# Sheet1.net
KiCad netlist of a schematic drawn in Altium Designer
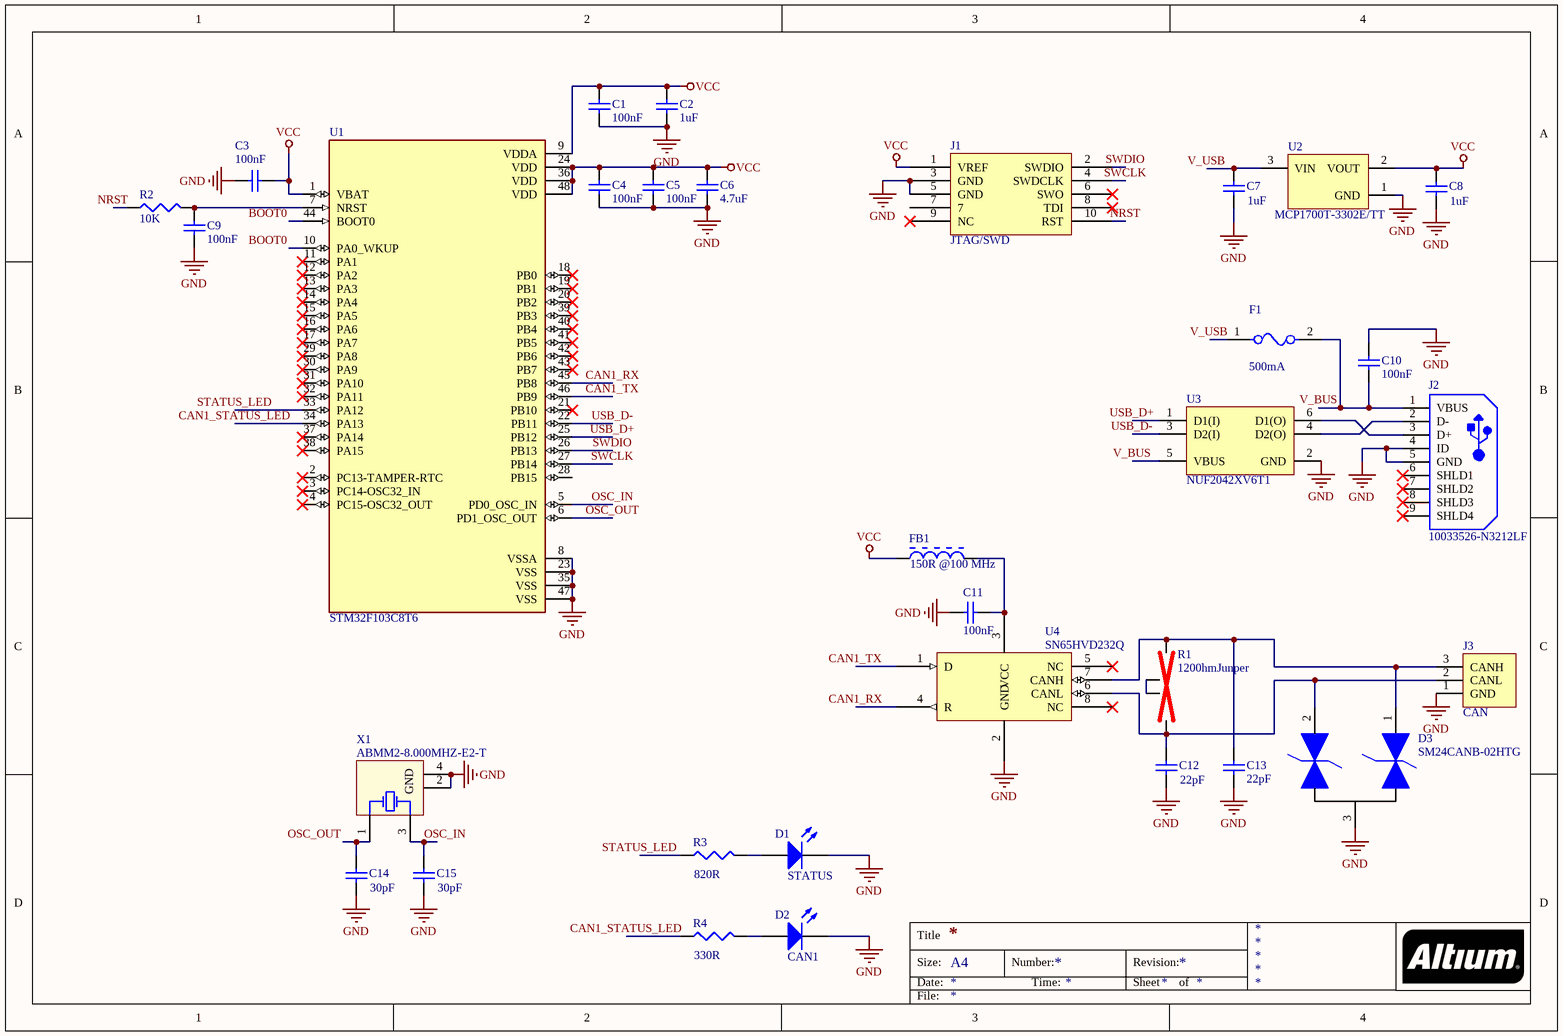
[diagram p0: Sheet1.SchDoc]

(export (version "E")
  (design (tool "Eeschema 10.0.6"))
  (components
    (comp (ref "C1")
      (value "100nF")
      (footprint "CAP0805")
      (description "Capacitor (Semiconductor SIM Model)")
      (fields (field (name "Comment") "Cap Semi") (field (name "PUBLISHER") "Altium Limited"))
      (libsource (lib "Miscellaneous Devices") (part "Cap Semi"))
    )
    (comp (ref "C2")
      (value "1uF")
      (footprint "CAP0805")
      (description "Capacitor (Semiconductor SIM Model)")
      (fields (field (name "Comment") "Cap Semi") (field (name "PUBLISHER") "Altium Limited"))
      (libsource (lib "Miscellaneous Devices") (part "Cap Semi"))
    )
    (comp (ref "C3")
      (value "100nF")
      (footprint "CAP0805")
      (description "Capacitor (Semiconductor SIM Model)")
      (fields (field (name "Comment") "Cap Semi") (field (name "PUBLISHER") "Altium Limited"))
      (libsource (lib "Miscellaneous Devices") (part "Cap Semi"))
    )
    (comp (ref "C4")
      (value "100nF")
      (footprint "CAP0805")
      (description "Capacitor (Semiconductor SIM Model)")
      (fields (field (name "Comment") "Cap Semi") (field (name "PUBLISHER") "Altium Limited"))
      (libsource (lib "Miscellaneous Devices") (part "Cap Semi"))
    )
    (comp (ref "C5")
      (value "100nF")
      (footprint "CAP0805")
      (description "Capacitor (Semiconductor SIM Model)")
      (fields (field (name "Comment") "Cap Semi") (field (name "PUBLISHER") "Altium Limited"))
      (libsource (lib "Miscellaneous Devices") (part "Cap Semi"))
    )
    (comp (ref "C6")
      (value "4.7uF")
      (footprint "CAP0805")
      (description "Capacitor (Semiconductor SIM Model)")
      (fields (field (name "Comment") "Cap Semi") (field (name "PUBLISHER") "Altium Limited"))
      (libsource (lib "Miscellaneous Devices") (part "Cap Semi"))
    )
    (comp (ref "C7")
      (value "1uF")
      (footprint "CAP0805")
      (description "Capacitor (Semiconductor SIM Model)")
      (fields (field (name "Comment") "Cap Semi") (field (name "PUBLISHER") "Altium Limited"))
      (libsource (lib "Miscellaneous Devices") (part "Cap Semi"))
    )
    (comp (ref "C8")
      (value "1uF")
      (footprint "CAP0805")
      (description "Capacitor (Semiconductor SIM Model)")
      (fields (field (name "Comment") "Cap Semi") (field (name "PUBLISHER") "Altium Limited"))
      (libsource (lib "Miscellaneous Devices") (part "Cap Semi"))
    )
    (comp (ref "C9")
      (value "100nF")
      (footprint "CAP0805")
      (description "Capacitor (Semiconductor SIM Model)")
      (fields (field (name "Comment") "Cap Semi") (field (name "PUBLISHER") "Altium Limited"))
      (libsource (lib "Miscellaneous Devices") (part "Cap Semi"))
    )
    (comp (ref "C10")
      (value "100nF")
      (footprint "CAP0805")
      (description "Capacitor (Semiconductor SIM Model)")
      (fields (field (name "Comment") "Cap Semi") (field (name "PUBLISHER") "Altium Limited"))
      (libsource (lib "Miscellaneous Devices") (part "Cap Semi"))
    )
    (comp (ref "C11")
      (value "100nF")
      (footprint "CAP0805")
      (description "Capacitor (Semiconductor SIM Model)")
      (fields (field (name "Comment") "Cap Semi") (field (name "PUBLISHER") "Altium Limited"))
      (libsource (lib "Miscellaneous Devices") (part "Cap Semi"))
    )
    (comp (ref "C12")
      (value "22pF")
      (footprint "CAP0805")
      (description "Capacitor (Semiconductor SIM Model)")
      (fields (field (name "Comment") "Cap Semi") (field (name "PUBLISHER") "Altium Limited"))
      (libsource (lib "Miscellaneous Devices") (part "Cap Semi"))
    )
    (comp (ref "C13")
      (value "22pF")
      (footprint "CAP0805")
      (description "Capacitor (Semiconductor SIM Model)")
      (fields (field (name "Comment") "Cap Semi") (field (name "PUBLISHER") "Altium Limited"))
      (libsource (lib "Miscellaneous Devices") (part "Cap Semi"))
    )
    (comp (ref "C14")
      (value "30pF")
      (footprint "CAP0805")
      (description "Capacitor (Semiconductor SIM Model)")
      (fields (field (name "Comment") "Cap Semi") (field (name "PUBLISHER") "Altium Limited"))
      (libsource (lib "Miscellaneous Devices") (part "Cap Semi"))
    )
    (comp (ref "C15")
      (value "30pF")
      (footprint "CAP0805")
      (description "Capacitor (Semiconductor SIM Model)")
      (fields (field (name "Comment") "Cap Semi") (field (name "PUBLISHER") "Altium Limited"))
      (libsource (lib "Miscellaneous Devices") (part "Cap Semi"))
    )
    (comp (ref "D1")
      (value "STATUS")
      (footprint "0603_A")
      (description "SMD mono-color Chip LED, WL-SMCW, Red")
      (fields (field (name "MANUFACTURER") "Wuerth Elektronik") (field (name "PARTNUMBER") "150060RS75000"))
      (libsource (lib "Altium Content Vault") (part "WE-LED_K1A2-2"))
    )
    (comp (ref "D2")
      (value "CAN1")
      (footprint "0603_A")
      (description "SMD mono-color Chip LED, WL-SMCW, Green")
      (fields (field (name "PARTNUMBER") "150060GS75000") (field (name "MANUFACTURER") "Wuerth Elektronik"))
      (libsource (lib "Altium Content Vault") (part "WE-LED_K1A2-2"))
    )
    (comp (ref "D3")
      (value "SM24CANB-02HTG")
      (footprint "SOT-23-3")
      (libsource (lib "CAN-USB-Converter") (part "SM24CANB-02HTG"))
    )
    (comp (ref "F1")
      (value "500mA")
      (footprint "FP-0154-MFG")
      (description "FUSE BOARD MNT 500MA 125VAC/VDC")
      (fields
        (field (name "OCTOPART") "https://octopart.com/0154.500drt-littelfuse-565915")
        (field (name "MANUFACTURER") "Littelfuse")
      )
      (libsource (lib "Altium Content Vault") (part "5bcf9b9f640e542cf0359d10258e979"))
    )
    (comp (ref "FB1")
      (value "150R @100 MHz")
      (footprint "MURA-BLM21-H1-CHIP-2_V")
      (fields (field (name "MANUFACTURER") "Murata") (field (name "PARTNUMBER") "BLM21AG151SN1D"))
      (libsource (lib "Altium Content Vault") (part "MURA-FB-2"))
    )
    (comp (ref "J1")
      (value "JTAG/SWD")
      (footprint "61301021021")
      (libsource (lib "CAN-USB-Converter") (part "JTAG/SWD"))
    )
    (comp (ref "J2")
      (value "10033526-N3212LF")
      (footprint "FCI-10033526-N3212LF_V")
      (description "Mini USB B-Type, 5-Pin SMD, RoHS, Tape and Reel")
      (libsource (lib "Altium Content Vault") (part "USB-5-4SHLD"))
    )
    (comp (ref "J3")
      (value "CAN")
      (footprint "3PIN-Screw-Terminal")
      (libsource (lib "CAN-USB-Converter") (part "3PIN-Screw-Terminal"))
    )
    (comp (ref "R1")
      (value "1200hmJunper")
      (footprint "120ohmJumper")
      (libsource (lib "CAN-USB-Converter") (part "1200hmJunper"))
    )
    (comp (ref "R2")
      (value "10K")
      (footprint "RES0805")
      (description "Resistor")
      (fields (field (name "Comment") "Res3") (field (name "PUBLISHER") "Altium Limited"))
      (libsource (lib "Miscellaneous Devices") (part "Res3"))
    )
    (comp (ref "R3")
      (value "820R")
      (footprint "RES0805")
      (description "Resistor")
      (fields (field (name "Comment") "Res3") (field (name "PUBLISHER") "Altium Limited"))
      (libsource (lib "Miscellaneous Devices") (part "Res3"))
    )
    (comp (ref "R4")
      (value "330R")
      (footprint "RES0805")
      (description "Resistor")
      (fields (field (name "Comment") "Res3") (field (name "PUBLISHER") "Altium Limited"))
      (libsource (lib "Miscellaneous Devices") (part "Res3"))
    )
    (comp (ref "U1")
      (value "STM32F103C8T6")
      (footprint "STM32F103C8T6")
      (description "ARMÂ® CortexÂ®-M3 STM32F1 Microcontroller IC 32-Bit 72MHz 64KB _64K x 8_ FLASH")
      (fields (field (name "MF") "STMicroelectronics"))
      (libsource (lib "CAN-USB-Converter") (part "STM32F103C8T6"))
    )
    (comp (ref "U2")
      (value "MCP1700T-3302E/TT")
      (footprint "SOT-23-TT3_N")
      (description "Low Quiescent Current LDO, 3-Pin SOT-23, Extended Temperature, Tape and Reel")
      (libsource (lib "Altium Content Vault") (part "PM-LINEREG-MCP1700-IL3"))
    )
    (comp (ref "U3")
      (value "NUF2042XV6T1")
      (footprint "ONSC-SOT-563-6-463A-01_V")
      (description "USB Upstream Terminator with ESD Protection, 6-Pin SOT-563, Pb-Free, Tape and Reel")
      (fields (field (name "MANUFACTURER") "On Semiconductor"))
      (libsource (lib "Altium Content Vault") (part "ONSC-EMI-NUF20XXXV6-6"))
    )
    (comp (ref "U4")
      (value "SN65HVD232Q")
      (footprint "SO-8_S")
      (libsource (lib "CAN-USB-Converter") (part "SN65HVD232Q"))
    )
    (comp (ref "X1")
      (value "ABMM2-8.000MHZ-E2-T")
      (footprint "ABRA-ABMM2-4_V")
      (fields (field (name "MANUFACTURER") "Abracon"))
      (libsource (lib "Altium Content Vault") (part "ABRA-XTAL_1-3-4"))
    )
  )
  (nets
    (net (code "1") (name "/BOOT0") (class "Default")
      (node (ref "U1") (pin "10") (pinfunction "PA0_WKUP_10") (pintype "bidirectional"))
      (node (ref "U1") (pin "44") (pinfunction "BOOT0_44") (pintype "input"))
    )
    (net (code "2") (name "/CAN1_RX") (class "Default")
      (node (ref "U1") (pin "45") (pinfunction "PB8_45") (pintype "bidirectional"))
      (node (ref "U4") (pin "4") (pinfunction "R_4") (pintype "output"))
    )
    (net (code "3") (name "/CAN1_STATUS_LED") (class "Default")
      (node (ref "R4") (pin "1") (pinfunction "1_1") (pintype "passive"))
      (node (ref "U1") (pin "34") (pinfunction "PA13_34") (pintype "bidirectional"))
    )
    (net (code "4") (name "/CAN1_TX") (class "Default")
      (node (ref "U1") (pin "46") (pinfunction "PB9_46") (pintype "bidirectional"))
      (node (ref "U4") (pin "1") (pinfunction "D_1") (pintype "input"))
    )
    (net (code "5") (name "/NRST") (class "Default")
      (node (ref "J1") (pin "10") (pinfunction "RST_10") (pintype "passive"))
      (node (ref "R2") (pin "2") (pinfunction "2_2") (pintype "passive"))
    )
    (net (code "6") (name "/OSC_IN") (class "Default")
      (node (ref "C15") (pin "2") (pinfunction "2_2") (pintype "passive"))
      (node (ref "U1") (pin "5") (pinfunction "PD0_OSC_IN_5") (pintype "bidirectional"))
      (node (ref "X1") (pin "3") (pinfunction "X2_3") (pintype "passive"))
    )
    (net (code "7") (name "/OSC_OUT") (class "Default")
      (node (ref "C14") (pin "2") (pinfunction "2_2") (pintype "passive"))
      (node (ref "U1") (pin "6") (pinfunction "PD1_OSC_OUT_6") (pintype "bidirectional"))
      (node (ref "X1") (pin "1") (pinfunction "X1_1") (pintype "passive"))
    )
    (net (code "8") (name "/STATUS_LED") (class "Default")
      (node (ref "R3") (pin "1") (pinfunction "1_1") (pintype "passive"))
      (node (ref "U1") (pin "33") (pinfunction "PA12_33") (pintype "bidirectional"))
    )
    (net (code "9") (name "/SWCLK") (class "Default")
      (node (ref "J1") (pin "4") (pinfunction "SWDCLK_4") (pintype "passive"))
      (node (ref "U1") (pin "27") (pinfunction "PB14_27") (pintype "bidirectional"))
    )
    (net (code "10") (name "/SWDIO") (class "Default")
      (node (ref "J1") (pin "2") (pinfunction "SWDIO_2") (pintype "passive"))
      (node (ref "U1") (pin "26") (pinfunction "PB13_26") (pintype "bidirectional"))
    )
    (net (code "11") (name "/USB_D+") (class "Default")
      (node (ref "U1") (pin "25") (pinfunction "PB12_25") (pintype "bidirectional"))
      (node (ref "U3") (pin "1") (pinfunction "D1(I)_1") (pintype "passive"))
    )
    (net (code "12") (name "/USB_D-") (class "Default")
      (node (ref "U1") (pin "22") (pinfunction "PB11_22") (pintype "bidirectional"))
      (node (ref "U3") (pin "3") (pinfunction "D2(I)_3") (pintype "passive"))
    )
    (net (code "13") (name "/V_BUS") (class "Default")
      (node (ref "C10") (pin "2") (pinfunction "2_2") (pintype "passive"))
      (node (ref "F1") (pin "2") (pinfunction "2_2") (pintype "passive"))
      (node (ref "J2") (pin "1") (pinfunction "VBUS_1") (pintype "power_in"))
      (node (ref "U3") (pin "5") (pinfunction "VBUS_5") (pintype "power_in"))
    )
    (net (code "14") (name "/V_USB") (class "Default")
      (node (ref "C7") (pin "2") (pinfunction "2_2") (pintype "passive"))
      (node (ref "F1") (pin "1") (pinfunction "1_1") (pintype "passive"))
      (node (ref "U2") (pin "3") (pinfunction "VIN_3") (pintype "power_in"))
    )
    (net (code "15") (name "GND") (class "Default")
      (node (ref "C1") (pin "1") (pinfunction "1_1") (pintype "passive"))
      (node (ref "C10") (pin "1") (pinfunction "1_1") (pintype "passive"))
      (node (ref "C11") (pin "1") (pinfunction "1_1") (pintype "passive"))
      (node (ref "C12") (pin "1") (pinfunction "1_1") (pintype "passive"))
      (node (ref "C13") (pin "2") (pinfunction "2_2") (pintype "passive"))
      (node (ref "C14") (pin "1") (pinfunction "1_1") (pintype "passive"))
      (node (ref "C15") (pin "1") (pinfunction "1_1") (pintype "passive"))
      (node (ref "C2") (pin "1") (pinfunction "1_1") (pintype "passive"))
      (node (ref "C3") (pin "1") (pinfunction "1_1") (pintype "passive"))
      (node (ref "C4") (pin "1") (pinfunction "1_1") (pintype "passive"))
      (node (ref "C5") (pin "1") (pinfunction "1_1") (pintype "passive"))
      (node (ref "C6") (pin "1") (pinfunction "1_1") (pintype "passive"))
      (node (ref "C7") (pin "1") (pinfunction "1_1") (pintype "passive"))
      (node (ref "C8") (pin "1") (pinfunction "1_1") (pintype "passive"))
      (node (ref "C9") (pin "1") (pinfunction "1_1") (pintype "passive"))
      (node (ref "D1") (pin "1") (pinfunction "K_1") (pintype "passive"))
      (node (ref "D2") (pin "1") (pinfunction "K_1") (pintype "passive"))
      (node (ref "D3") (pin "3") (pinfunction "3_3") (pintype "passive"))
      (node (ref "J1") (pin "3") (pinfunction "GND_3") (pintype "passive"))
      (node (ref "J1") (pin "5") (pinfunction "GND_5") (pintype "passive"))
      (node (ref "J2") (pin "4") (pinfunction "ID_4") (pintype "passive"))
      (node (ref "J2") (pin "5") (pinfunction "GND_5") (pintype "power_in"))
      (node (ref "J3") (pin "1") (pinfunction "GND_1") (pintype "passive"))
      (node (ref "U1") (pin "23") (pinfunction "VSS_23") (pintype "power_in"))
      (node (ref "U1") (pin "35") (pinfunction "VSS_35") (pintype "power_in"))
      (node (ref "U1") (pin "47") (pinfunction "VSS_47") (pintype "power_in"))
      (node (ref "U1") (pin "8") (pinfunction "VSSA_8") (pintype "power_in"))
      (node (ref "U2") (pin "1") (pinfunction "GND_1") (pintype "power_in"))
      (node (ref "U3") (pin "2") (pinfunction "GND_2") (pintype "power_in"))
      (node (ref "U4") (pin "2") (pinfunction "GND_2") (pintype "passive"))
      (node (ref "X1") (pin "2") (pinfunction "GND_2") (pintype "power_in"))
      (node (ref "X1") (pin "4") (pinfunction "GND_4") (pintype "power_in"))
    )
    (net (code "16") (name "Net-(D1-A)") (class "Default")
      (node (ref "D1") (pin "2") (pinfunction "A_2") (pintype "passive"))
      (node (ref "R3") (pin "2") (pinfunction "2_2") (pintype "passive"))
    )
    (net (code "17") (name "Net-(D2-A)") (class "Default")
      (node (ref "D2") (pin "2") (pinfunction "A_2") (pintype "passive"))
      (node (ref "R4") (pin "2") (pinfunction "2_2") (pintype "passive"))
    )
    (net (code "18") (name "Net-(J2-D+)") (class "Default")
      (node (ref "J2") (pin "3") (pinfunction "D+_3") (pintype "passive"))
      (node (ref "U3") (pin "6") (pinfunction "D1(O)_6") (pintype "passive"))
    )
    (net (code "19") (name "Net-(J2-D-)") (class "Default")
      (node (ref "J2") (pin "2") (pinfunction "D-_2") (pintype "passive"))
      (node (ref "U3") (pin "4") (pinfunction "D2(O)_4") (pintype "passive"))
    )
    (net (code "20") (name "Net-(J3-CANH)") (class "Default")
      (node (ref "C13") (pin "1") (pinfunction "1_1") (pintype "passive"))
      (node (ref "D3") (pin "1") (pinfunction "1_1") (pintype "passive"))
      (node (ref "J3") (pin "3") (pinfunction "CANH_3") (pintype "passive"))
      (node (ref "R1") (pin "1") (pinfunction "1_1") (pintype "passive"))
      (node (ref "U4") (pin "7") (pinfunction "CANH_7") (pintype "bidirectional"))
    )
    (net (code "21") (name "Net-(J3-CANL)") (class "Default")
      (node (ref "C12") (pin "2") (pinfunction "2_2") (pintype "passive"))
      (node (ref "D3") (pin "2") (pinfunction "2_2") (pintype "passive"))
      (node (ref "J3") (pin "2") (pinfunction "CANL_2") (pintype "passive"))
      (node (ref "R1") (pin "2") (pinfunction "1_2") (pintype "passive"))
      (node (ref "U4") (pin "6") (pinfunction "CANL_6") (pintype "bidirectional"))
    )
    (net (code "22") (name "Net-(R1-Pad3)") (class "Default")
      (node (ref "R1") (pin "3") (pinfunction "3_3") (pintype "passive"))
      (node (ref "R1") (pin "4") (pinfunction "4_4") (pintype "passive"))
    )
    (net (code "23") (name "Net-(U1-NRST)") (class "Default")
      (node (ref "C9") (pin "2") (pinfunction "2_2") (pintype "passive"))
      (node (ref "R2") (pin "1") (pinfunction "1_1") (pintype "passive"))
      (node (ref "U1") (pin "7") (pinfunction "NRST_7") (pintype "input"))
    )
    (net (code "24") (name "Net-(U4-VCC)") (class "Default")
      (node (ref "C11") (pin "2") (pinfunction "2_2") (pintype "passive"))
      (node (ref "FB1") (pin "2") (pinfunction "2_2") (pintype "passive"))
      (node (ref "U4") (pin "3") (pinfunction "VCC_3") (pintype "passive"))
    )
    (net (code "25") (name "VCC") (class "Default")
      (node (ref "C1") (pin "2") (pinfunction "2_2") (pintype "passive"))
      (node (ref "C2") (pin "2") (pinfunction "2_2") (pintype "passive"))
      (node (ref "C3") (pin "2") (pinfunction "2_2") (pintype "passive"))
      (node (ref "C4") (pin "2") (pinfunction "2_2") (pintype "passive"))
      (node (ref "C5") (pin "2") (pinfunction "2_2") (pintype "passive"))
      (node (ref "C6") (pin "2") (pinfunction "2_2") (pintype "passive"))
      (node (ref "C8") (pin "2") (pinfunction "2_2") (pintype "passive"))
      (node (ref "FB1") (pin "1") (pinfunction "1_1") (pintype "passive"))
      (node (ref "J1") (pin "1") (pinfunction "VREF_1") (pintype "passive"))
      (node (ref "U1") (pin "1") (pinfunction "VBAT_1") (pintype "bidirectional"))
      (node (ref "U1") (pin "24") (pinfunction "VDD_24") (pintype "power_in"))
      (node (ref "U1") (pin "36") (pinfunction "VDD_36") (pintype "power_in"))
      (node (ref "U1") (pin "48") (pinfunction "VDD_48") (pintype "power_in"))
      (node (ref "U1") (pin "9") (pinfunction "VDDA_9") (pintype "power_in"))
      (node (ref "U2") (pin "2") (pinfunction "VOUT_2") (pintype "power_in"))
    )
    (net (code "26") (name "unconnected-(J1-NC-Pad9)") (class "Default")
      (node (ref "J1") (pin "9") (pinfunction "NC_9") (pintype "passive+no_connect"))
    )
    (net (code "27") (name "unconnected-(J1-Pad7)") (class "Default")
      (node (ref "J1") (pin "7") (pinfunction "7_7") (pintype "passive"))
    )
    (net (code "28") (name "unconnected-(J1-SWO-Pad6)") (class "Default")
      (node (ref "J1") (pin "6") (pinfunction "SWO_6") (pintype "passive+no_connect"))
    )
    (net (code "29") (name "unconnected-(J1-TDI-Pad8)") (class "Default")
      (node (ref "J1") (pin "8") (pinfunction "TDI_8") (pintype "passive+no_connect"))
    )
    (net (code "30") (name "unconnected-(J2-SHLD1-Pad6)") (class "Default")
      (node (ref "J2") (pin "6") (pinfunction "SHLD1_6") (pintype "passive+no_connect"))
    )
    (net (code "31") (name "unconnected-(J2-SHLD2-Pad7)") (class "Default")
      (node (ref "J2") (pin "7") (pinfunction "SHLD2_7") (pintype "passive+no_connect"))
    )
    (net (code "32") (name "unconnected-(J2-SHLD3-Pad8)") (class "Default")
      (node (ref "J2") (pin "8") (pinfunction "SHLD3_8") (pintype "passive+no_connect"))
    )
    (net (code "33") (name "unconnected-(J2-SHLD4-Pad9)") (class "Default")
      (node (ref "J2") (pin "9") (pinfunction "SHLD4_9") (pintype "passive+no_connect"))
    )
    (net (code "34") (name "unconnected-(U1-PA1-Pad11)") (class "Default")
      (node (ref "U1") (pin "11") (pinfunction "PA1_11") (pintype "bidirectional+no_connect"))
    )
    (net (code "35") (name "unconnected-(U1-PA2-Pad12)") (class "Default")
      (node (ref "U1") (pin "12") (pinfunction "PA2_12") (pintype "bidirectional+no_connect"))
    )
    (net (code "36") (name "unconnected-(U1-PA3-Pad13)") (class "Default")
      (node (ref "U1") (pin "13") (pinfunction "PA3_13") (pintype "bidirectional+no_connect"))
    )
    (net (code "37") (name "unconnected-(U1-PA4-Pad14)") (class "Default")
      (node (ref "U1") (pin "14") (pinfunction "PA4_14") (pintype "bidirectional+no_connect"))
    )
    (net (code "38") (name "unconnected-(U1-PA5-Pad15)") (class "Default")
      (node (ref "U1") (pin "15") (pinfunction "PA5_15") (pintype "bidirectional+no_connect"))
    )
    (net (code "39") (name "unconnected-(U1-PA6-Pad16)") (class "Default")
      (node (ref "U1") (pin "16") (pinfunction "PA6_16") (pintype "bidirectional+no_connect"))
    )
    (net (code "40") (name "unconnected-(U1-PA7-Pad17)") (class "Default")
      (node (ref "U1") (pin "17") (pinfunction "PA7_17") (pintype "bidirectional+no_connect"))
    )
    (net (code "41") (name "unconnected-(U1-PA8-Pad29)") (class "Default")
      (node (ref "U1") (pin "29") (pinfunction "PA8_29") (pintype "bidirectional+no_connect"))
    )
    (net (code "42") (name "unconnected-(U1-PA9-Pad30)") (class "Default")
      (node (ref "U1") (pin "30") (pinfunction "PA9_30") (pintype "bidirectional+no_connect"))
    )
    (net (code "43") (name "unconnected-(U1-PA10-Pad31)") (class "Default")
      (node (ref "U1") (pin "31") (pinfunction "PA10_31") (pintype "bidirectional+no_connect"))
    )
    (net (code "44") (name "unconnected-(U1-PA11-Pad32)") (class "Default")
      (node (ref "U1") (pin "32") (pinfunction "PA11_32") (pintype "bidirectional+no_connect"))
    )
    (net (code "45") (name "unconnected-(U1-PA14-Pad37)") (class "Default")
      (node (ref "U1") (pin "37") (pinfunction "PA14_37") (pintype "bidirectional+no_connect"))
    )
    (net (code "46") (name "unconnected-(U1-PA15-Pad38)") (class "Default")
      (node (ref "U1") (pin "38") (pinfunction "PA15_38") (pintype "bidirectional+no_connect"))
    )
    (net (code "47") (name "unconnected-(U1-PB0-Pad18)") (class "Default")
      (node (ref "U1") (pin "18") (pinfunction "PB0_18") (pintype "bidirectional+no_connect"))
    )
    (net (code "48") (name "unconnected-(U1-PB1-Pad19)") (class "Default")
      (node (ref "U1") (pin "19") (pinfunction "PB1_19") (pintype "bidirectional+no_connect"))
    )
    (net (code "49") (name "unconnected-(U1-PB2-Pad20)") (class "Default")
      (node (ref "U1") (pin "20") (pinfunction "PB2_20") (pintype "bidirectional+no_connect"))
    )
    (net (code "50") (name "unconnected-(U1-PB3-Pad39)") (class "Default")
      (node (ref "U1") (pin "39") (pinfunction "PB3_39") (pintype "bidirectional+no_connect"))
    )
    (net (code "51") (name "unconnected-(U1-PB4-Pad40)") (class "Default")
      (node (ref "U1") (pin "40") (pinfunction "PB4_40") (pintype "bidirectional+no_connect"))
    )
    (net (code "52") (name "unconnected-(U1-PB5-Pad41)") (class "Default")
      (node (ref "U1") (pin "41") (pinfunction "PB5_41") (pintype "bidirectional+no_connect"))
    )
    (net (code "53") (name "unconnected-(U1-PB6-Pad42)") (class "Default")
      (node (ref "U1") (pin "42") (pinfunction "PB6_42") (pintype "bidirectional+no_connect"))
    )
    (net (code "54") (name "unconnected-(U1-PB7-Pad43)") (class "Default")
      (node (ref "U1") (pin "43") (pinfunction "PB7_43") (pintype "bidirectional+no_connect"))
    )
    (net (code "55") (name "unconnected-(U1-PB10-Pad21)") (class "Default")
      (node (ref "U1") (pin "21") (pinfunction "PB10_21") (pintype "bidirectional+no_connect"))
    )
    (net (code "56") (name "unconnected-(U1-PB15-Pad28)") (class "Default")
      (node (ref "U1") (pin "28") (pinfunction "PB15_28") (pintype "bidirectional"))
    )
    (net (code "57") (name "unconnected-(U1-PC13-TAMPER-RTC-Pad2)") (class "Default")
      (node (ref "U1") (pin "2") (pinfunction "PC13-TAMPER-RTC_2") (pintype "bidirectional+no_connect"))
    )
    (net (code "58") (name "unconnected-(U1-PC14-OSC32_IN-Pad3)") (class "Default")
      (node (ref "U1") (pin "3") (pinfunction "PC14-OSC32_IN_3") (pintype "bidirectional+no_connect"))
    )
    (net (code "59") (name "unconnected-(U1-PC15-OSC32_OUT-Pad4)") (class "Default")
      (node (ref "U1") (pin "4") (pinfunction "PC15-OSC32_OUT_4") (pintype "bidirectional+no_connect"))
    )
    (net (code "60") (name "unconnected-(U4-NC-Pad5)") (class "Default")
      (node (ref "U4") (pin "5") (pinfunction "NC_5") (pintype "passive+no_connect"))
    )
    (net (code "61") (name "unconnected-(U4-NC-Pad8)") (class "Default")
      (node (ref "U4") (pin "8") (pinfunction "NC_8") (pintype "passive+no_connect"))
    )
  )
)
